# USBdimmer-breakout.net
KiCad netlist of a schematic drawn in EAGLE
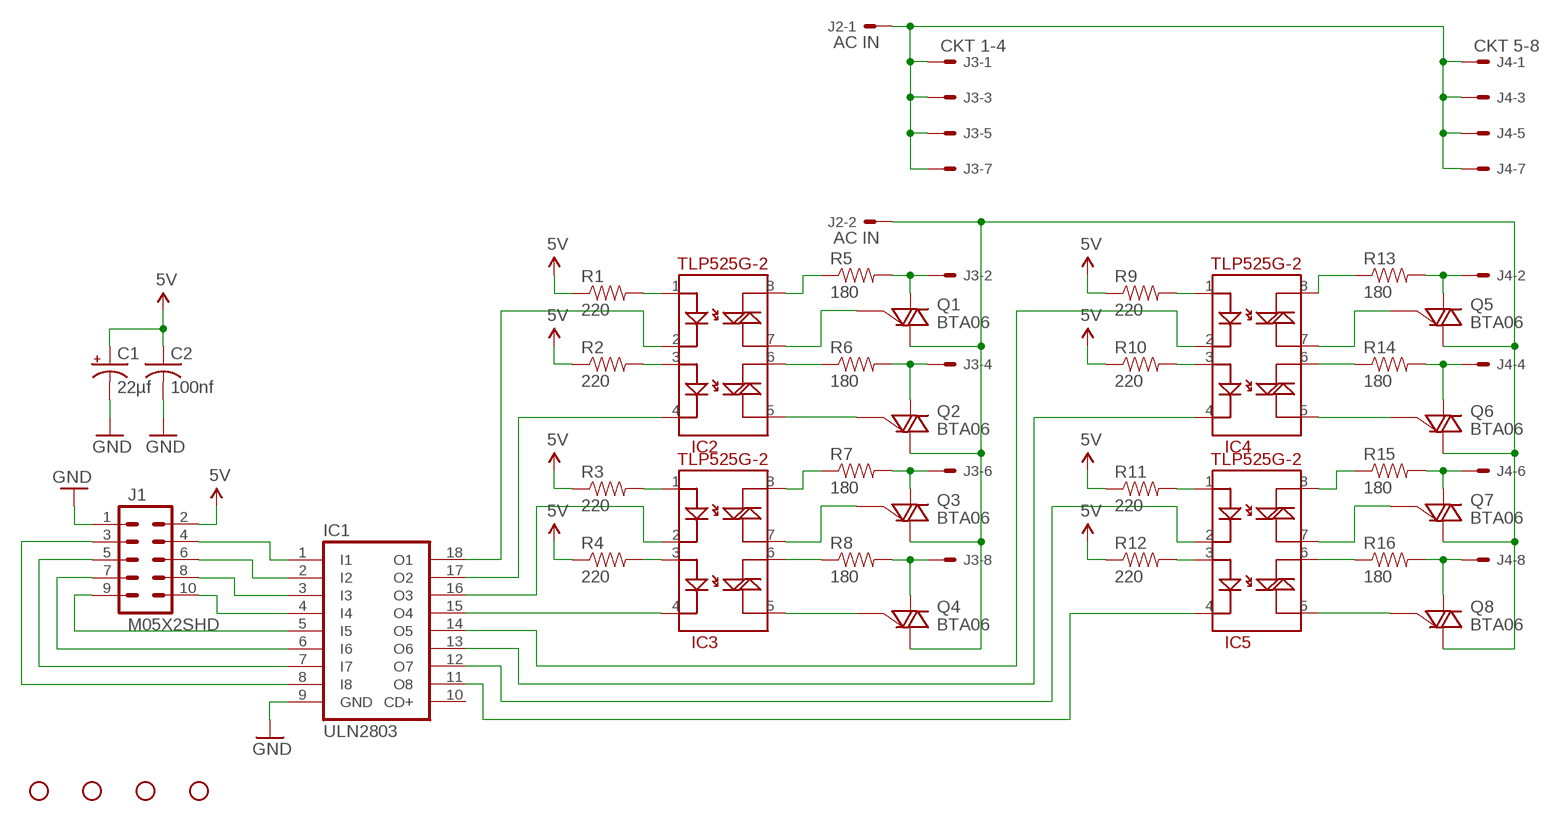
[diagram p0: schematic, sheet 1]

(export (version "E")
  (design (tool "Eeschema 10.0.6"))
  (components
    (comp (ref "C1")
      (value "22µf")
      (footprint "eagle-import:E5-8,5")
      (libsource (lib "eagle-import") (part "CPOL-USE5-8.5"))
    )
    (comp (ref "C2")
      (value "100nf")
      (footprint "eagle-import:C025-030X050")
      (libsource (lib "eagle-import") (part "C-US025-030X050"))
    )
    (comp (ref "IC1")
      (value "ULN2803")
      (footprint "eagle-import:DIL18")
      (libsource (lib "eagle-import") (part "ULN2803A"))
    )
    (comp (ref "IC2")
      (value "TLP525G-2")
      (footprint "eagle-import:DIL08")
      (libsource (lib "eagle-import") (part "TLP525G-2"))
    )
    (comp (ref "IC3")
      (value "TLP525G-2")
      (footprint "eagle-import:DIL08")
      (libsource (lib "eagle-import") (part "TLP525G-2"))
    )
    (comp (ref "IC4")
      (value "TLP525G-2")
      (footprint "eagle-import:DIL08")
      (libsource (lib "eagle-import") (part "TLP525G-2"))
    )
    (comp (ref "IC5")
      (value "TLP525G-2")
      (footprint "eagle-import:DIL08")
      (libsource (lib "eagle-import") (part "TLP525G-2"))
    )
    (comp (ref "J1")
      (value "M05X2SHD")
      (footprint "eagle-import:2X5-SHROUDED")
      (libsource (lib "eagle-import") (part "M05X2SHD"))
    )
    (comp (ref "J2")
      (value "AC IN")
      (footprint "eagle-import:KK-156-2")
      (libsource (lib "eagle-import") (part "KK-156-2"))
    )
    (comp (ref "J3")
      (value "CKT 1-4")
      (footprint "eagle-import:KK-156-8")
      (libsource (lib "eagle-import") (part "KK-156-8"))
    )
    (comp (ref "J4")
      (value "CKT 5-8")
      (footprint "eagle-import:KK-156-8")
      (libsource (lib "eagle-import") (part "KK-156-8"))
    )
    (comp (ref "Q1")
      (value "BTA06")
      (footprint "eagle-import:TO220BV")
      (libsource (lib "eagle-import") (part "BTA06"))
    )
    (comp (ref "Q2")
      (value "BTA06")
      (footprint "eagle-import:TO220BV")
      (libsource (lib "eagle-import") (part "BTA06"))
    )
    (comp (ref "Q3")
      (value "BTA06")
      (footprint "eagle-import:TO220BV")
      (libsource (lib "eagle-import") (part "BTA06"))
    )
    (comp (ref "Q4")
      (value "BTA06")
      (footprint "eagle-import:TO220BV")
      (libsource (lib "eagle-import") (part "BTA06"))
    )
    (comp (ref "Q5")
      (value "BTA06")
      (footprint "eagle-import:TO220BV")
      (libsource (lib "eagle-import") (part "BTA06"))
    )
    (comp (ref "Q6")
      (value "BTA06")
      (footprint "eagle-import:TO220BV")
      (libsource (lib "eagle-import") (part "BTA06"))
    )
    (comp (ref "Q7")
      (value "BTA06")
      (footprint "eagle-import:TO220BV")
      (libsource (lib "eagle-import") (part "BTA06"))
    )
    (comp (ref "Q8")
      (value "BTA06")
      (footprint "eagle-import:TO220BV")
      (libsource (lib "eagle-import") (part "BTA06"))
    )
    (comp (ref "R1")
      (value "220")
      (footprint "eagle-import:AXIAL-0.4")
      (libsource (lib "eagle-import") (part "RESISTORPTH-1/4W"))
    )
    (comp (ref "R2")
      (value "220")
      (footprint "eagle-import:AXIAL-0.4")
      (libsource (lib "eagle-import") (part "RESISTORPTH-1/4W"))
    )
    (comp (ref "R3")
      (value "220")
      (footprint "eagle-import:AXIAL-0.4")
      (libsource (lib "eagle-import") (part "RESISTORPTH-1/4W"))
    )
    (comp (ref "R4")
      (value "220")
      (footprint "eagle-import:AXIAL-0.4")
      (libsource (lib "eagle-import") (part "RESISTORPTH-1/4W"))
    )
    (comp (ref "R5")
      (value "180")
      (footprint "eagle-import:AXIAL-0.4")
      (libsource (lib "eagle-import") (part "RESISTORPTH-1/4W"))
    )
    (comp (ref "R6")
      (value "180")
      (footprint "eagle-import:AXIAL-0.4")
      (libsource (lib "eagle-import") (part "RESISTORPTH-1/4W"))
    )
    (comp (ref "R7")
      (value "180")
      (footprint "eagle-import:AXIAL-0.4")
      (libsource (lib "eagle-import") (part "RESISTORPTH-1/4W"))
    )
    (comp (ref "R8")
      (value "180")
      (footprint "eagle-import:AXIAL-0.4")
      (libsource (lib "eagle-import") (part "RESISTORPTH-1/4W"))
    )
    (comp (ref "R9")
      (value "220")
      (footprint "eagle-import:AXIAL-0.4")
      (libsource (lib "eagle-import") (part "RESISTORPTH-1/4W"))
    )
    (comp (ref "R10")
      (value "220")
      (footprint "eagle-import:AXIAL-0.4")
      (libsource (lib "eagle-import") (part "RESISTORPTH-1/4W"))
    )
    (comp (ref "R11")
      (value "220")
      (footprint "eagle-import:AXIAL-0.4")
      (libsource (lib "eagle-import") (part "RESISTORPTH-1/4W"))
    )
    (comp (ref "R12")
      (value "220")
      (footprint "eagle-import:AXIAL-0.4")
      (libsource (lib "eagle-import") (part "RESISTORPTH-1/4W"))
    )
    (comp (ref "R13")
      (value "180")
      (footprint "eagle-import:AXIAL-0.4")
      (libsource (lib "eagle-import") (part "RESISTORPTH-1/4W"))
    )
    (comp (ref "R14")
      (value "180")
      (footprint "eagle-import:AXIAL-0.4")
      (libsource (lib "eagle-import") (part "RESISTORPTH-1/4W"))
    )
    (comp (ref "R15")
      (value "180")
      (footprint "eagle-import:AXIAL-0.4")
      (libsource (lib "eagle-import") (part "RESISTORPTH-1/4W"))
    )
    (comp (ref "R16")
      (value "180")
      (footprint "eagle-import:AXIAL-0.4")
      (libsource (lib "eagle-import") (part "RESISTORPTH-1/4W"))
    )
    (comp (ref "STANDOFF1")
      (value "STAND-OFF")
      (footprint "eagle-import:STAND-OFF")
      (libsource (lib "eagle-import") (part "STAND-OFF"))
    )
    (comp (ref "STANDOFF2")
      (value "STAND-OFF")
      (footprint "eagle-import:STAND-OFF")
      (libsource (lib "eagle-import") (part "STAND-OFF"))
    )
    (comp (ref "STANDOFF3")
      (value "STAND-OFF")
      (footprint "eagle-import:STAND-OFF")
      (libsource (lib "eagle-import") (part "STAND-OFF"))
    )
    (comp (ref "STANDOFF4")
      (value "STAND-OFF")
      (footprint "eagle-import:STAND-OFF")
      (libsource (lib "eagle-import") (part "STAND-OFF"))
    )
  )
  (nets
    (net (code "1") (name "5V") (class "Default")
      (node (ref "C1") (pin "+") (pinfunction "+_+") (pintype "passive"))
      (node (ref "C2") (pin "1") (pinfunction "1_1") (pintype "passive"))
      (node (ref "J1") (pin "2") (pinfunction "2_2") (pintype "passive"))
      (node (ref "R1") (pin "P$1") (pinfunction "1_P$1") (pintype "passive"))
      (node (ref "R10") (pin "P$1") (pinfunction "1_P$1") (pintype "passive"))
      (node (ref "R11") (pin "P$1") (pinfunction "1_P$1") (pintype "passive"))
      (node (ref "R12") (pin "P$1") (pinfunction "1_P$1") (pintype "passive"))
      (node (ref "R2") (pin "P$1") (pinfunction "1_P$1") (pintype "passive"))
      (node (ref "R3") (pin "P$1") (pinfunction "1_P$1") (pintype "passive"))
      (node (ref "R4") (pin "P$1") (pinfunction "1_P$1") (pintype "passive"))
      (node (ref "R9") (pin "P$1") (pinfunction "1_P$1") (pintype "passive"))
    )
    (net (code "2") (name "GND") (class "Default")
      (node (ref "C1") (pin "-") (pinfunction "-_-") (pintype "passive"))
      (node (ref "C2") (pin "2") (pinfunction "2_2") (pintype "passive"))
      (node (ref "IC1") (pin "9") (pinfunction "GND_9") (pintype "power_in"))
      (node (ref "J1") (pin "1") (pinfunction "1_1") (pintype "passive"))
    )
    (net (code "3") (name "Net-(IC1-I1)") (class "Default")
      (node (ref "IC1") (pin "1") (pinfunction "I1_1") (pintype "input"))
      (node (ref "J1") (pin "4") (pinfunction "4_4") (pintype "passive"))
    )
    (net (code "4") (name "Net-(IC1-I2)") (class "Default")
      (node (ref "IC1") (pin "2") (pinfunction "I2_2") (pintype "input"))
      (node (ref "J1") (pin "6") (pinfunction "6_6") (pintype "passive"))
    )
    (net (code "5") (name "Net-(IC1-I3)") (class "Default")
      (node (ref "IC1") (pin "3") (pinfunction "I3_3") (pintype "input"))
      (node (ref "J1") (pin "8") (pinfunction "8_8") (pintype "passive"))
    )
    (net (code "6") (name "Net-(IC1-I4)") (class "Default")
      (node (ref "IC1") (pin "4") (pinfunction "I4_4") (pintype "input"))
      (node (ref "J1") (pin "10") (pinfunction "10_10") (pintype "passive"))
    )
    (net (code "7") (name "Net-(IC1-I5)") (class "Default")
      (node (ref "IC1") (pin "5") (pinfunction "I5_5") (pintype "input"))
      (node (ref "J1") (pin "9") (pinfunction "9_9") (pintype "passive"))
    )
    (net (code "8") (name "Net-(IC1-I6)") (class "Default")
      (node (ref "IC1") (pin "6") (pinfunction "I6_6") (pintype "input"))
      (node (ref "J1") (pin "7") (pinfunction "7_7") (pintype "passive"))
    )
    (net (code "9") (name "Net-(IC1-I7)") (class "Default")
      (node (ref "IC1") (pin "7") (pinfunction "I7_7") (pintype "input"))
      (node (ref "J1") (pin "5") (pinfunction "5_5") (pintype "passive"))
    )
    (net (code "10") (name "Net-(IC1-I8)") (class "Default")
      (node (ref "IC1") (pin "8") (pinfunction "I8_8") (pintype "input"))
      (node (ref "J1") (pin "3") (pinfunction "3_3") (pintype "passive"))
    )
    (net (code "11") (name "Net-(IC1-O1)") (class "Default")
      (node (ref "IC1") (pin "18") (pinfunction "O1_18") (pintype "open_collector"))
      (node (ref "IC2") (pin "2") (pinfunction "K1_2") (pintype "bidirectional"))
    )
    (net (code "12") (name "Net-(IC1-O2)") (class "Default")
      (node (ref "IC1") (pin "17") (pinfunction "O2_17") (pintype "open_collector"))
      (node (ref "IC2") (pin "4") (pinfunction "K2_4") (pintype "bidirectional"))
    )
    (net (code "13") (name "Net-(IC1-O3)") (class "Default")
      (node (ref "IC1") (pin "16") (pinfunction "O3_16") (pintype "open_collector"))
      (node (ref "IC3") (pin "2") (pinfunction "K1_2") (pintype "bidirectional"))
    )
    (net (code "14") (name "Net-(IC1-O4)") (class "Default")
      (node (ref "IC1") (pin "15") (pinfunction "O4_15") (pintype "open_collector"))
      (node (ref "IC3") (pin "4") (pinfunction "K2_4") (pintype "bidirectional"))
    )
    (net (code "15") (name "Net-(IC1-O5)") (class "Default")
      (node (ref "IC1") (pin "14") (pinfunction "O5_14") (pintype "open_collector"))
      (node (ref "IC4") (pin "2") (pinfunction "K1_2") (pintype "bidirectional"))
    )
    (net (code "16") (name "Net-(IC1-O6)") (class "Default")
      (node (ref "IC1") (pin "13") (pinfunction "O6_13") (pintype "open_collector"))
      (node (ref "IC4") (pin "4") (pinfunction "K2_4") (pintype "bidirectional"))
    )
    (net (code "17") (name "Net-(IC1-O7)") (class "Default")
      (node (ref "IC1") (pin "12") (pinfunction "O7_12") (pintype "open_collector"))
      (node (ref "IC5") (pin "2") (pinfunction "K1_2") (pintype "bidirectional"))
    )
    (net (code "18") (name "Net-(IC1-O8)") (class "Default")
      (node (ref "IC1") (pin "11") (pinfunction "O8_11") (pintype "open_collector"))
      (node (ref "IC5") (pin "4") (pinfunction "K2_4") (pintype "bidirectional"))
    )
    (net (code "19") (name "Net-(IC2-A1)") (class "Default")
      (node (ref "IC2") (pin "1") (pinfunction "A1_1") (pintype "bidirectional"))
      (node (ref "R1") (pin "P$2") (pinfunction "2_P$2") (pintype "passive"))
    )
    (net (code "20") (name "Net-(IC2-A2)") (class "Default")
      (node (ref "IC2") (pin "3") (pinfunction "A2_3") (pintype "bidirectional"))
      (node (ref "R2") (pin "P$2") (pinfunction "2_P$2") (pintype "passive"))
    )
    (net (code "21") (name "Net-(IC2-MT11)") (class "Default")
      (node (ref "IC2") (pin "8") (pinfunction "MT11_8") (pintype "bidirectional"))
      (node (ref "R5") (pin "P$1") (pinfunction "1_P$1") (pintype "passive"))
    )
    (net (code "22") (name "Net-(IC2-MT12)") (class "Default")
      (node (ref "IC2") (pin "7") (pinfunction "MT12_7") (pintype "bidirectional"))
      (node (ref "Q1") (pin "3") (pinfunction "G_3") (pintype "input"))
    )
    (net (code "23") (name "Net-(IC2-MT21)") (class "Default")
      (node (ref "IC2") (pin "6") (pinfunction "MT21_6") (pintype "bidirectional"))
      (node (ref "R6") (pin "P$1") (pinfunction "1_P$1") (pintype "passive"))
    )
    (net (code "24") (name "Net-(IC2-MT22)") (class "Default")
      (node (ref "IC2") (pin "5") (pinfunction "MT22_5") (pintype "bidirectional"))
      (node (ref "Q2") (pin "3") (pinfunction "G_3") (pintype "input"))
    )
    (net (code "25") (name "Net-(IC3-A1)") (class "Default")
      (node (ref "IC3") (pin "1") (pinfunction "A1_1") (pintype "bidirectional"))
      (node (ref "R3") (pin "P$2") (pinfunction "2_P$2") (pintype "passive"))
    )
    (net (code "26") (name "Net-(IC3-A2)") (class "Default")
      (node (ref "IC3") (pin "3") (pinfunction "A2_3") (pintype "bidirectional"))
      (node (ref "R4") (pin "P$2") (pinfunction "2_P$2") (pintype "passive"))
    )
    (net (code "27") (name "Net-(IC3-MT11)") (class "Default")
      (node (ref "IC3") (pin "8") (pinfunction "MT11_8") (pintype "bidirectional"))
      (node (ref "R7") (pin "P$1") (pinfunction "1_P$1") (pintype "passive"))
    )
    (net (code "28") (name "Net-(IC3-MT12)") (class "Default")
      (node (ref "IC3") (pin "7") (pinfunction "MT12_7") (pintype "bidirectional"))
      (node (ref "Q3") (pin "3") (pinfunction "G_3") (pintype "input"))
    )
    (net (code "29") (name "Net-(IC3-MT21)") (class "Default")
      (node (ref "IC3") (pin "6") (pinfunction "MT21_6") (pintype "bidirectional"))
      (node (ref "R8") (pin "P$1") (pinfunction "1_P$1") (pintype "passive"))
    )
    (net (code "30") (name "Net-(IC3-MT22)") (class "Default")
      (node (ref "IC3") (pin "5") (pinfunction "MT22_5") (pintype "bidirectional"))
      (node (ref "Q4") (pin "3") (pinfunction "G_3") (pintype "input"))
    )
    (net (code "31") (name "Net-(IC4-A1)") (class "Default")
      (node (ref "IC4") (pin "1") (pinfunction "A1_1") (pintype "bidirectional"))
      (node (ref "R9") (pin "P$2") (pinfunction "2_P$2") (pintype "passive"))
    )
    (net (code "32") (name "Net-(IC4-A2)") (class "Default")
      (node (ref "IC4") (pin "3") (pinfunction "A2_3") (pintype "bidirectional"))
      (node (ref "R10") (pin "P$2") (pinfunction "2_P$2") (pintype "passive"))
    )
    (net (code "33") (name "Net-(IC4-MT11)") (class "Default")
      (node (ref "IC4") (pin "8") (pinfunction "MT11_8") (pintype "bidirectional"))
      (node (ref "R13") (pin "P$1") (pinfunction "1_P$1") (pintype "passive"))
    )
    (net (code "34") (name "Net-(IC4-MT12)") (class "Default")
      (node (ref "IC4") (pin "7") (pinfunction "MT12_7") (pintype "bidirectional"))
      (node (ref "Q5") (pin "3") (pinfunction "G_3") (pintype "input"))
    )
    (net (code "35") (name "Net-(IC4-MT21)") (class "Default")
      (node (ref "IC4") (pin "6") (pinfunction "MT21_6") (pintype "bidirectional"))
      (node (ref "R14") (pin "P$1") (pinfunction "1_P$1") (pintype "passive"))
    )
    (net (code "36") (name "Net-(IC4-MT22)") (class "Default")
      (node (ref "IC4") (pin "5") (pinfunction "MT22_5") (pintype "bidirectional"))
      (node (ref "Q6") (pin "3") (pinfunction "G_3") (pintype "input"))
    )
    (net (code "37") (name "Net-(IC5-A1)") (class "Default")
      (node (ref "IC5") (pin "1") (pinfunction "A1_1") (pintype "bidirectional"))
      (node (ref "R11") (pin "P$2") (pinfunction "2_P$2") (pintype "passive"))
    )
    (net (code "38") (name "Net-(IC5-A2)") (class "Default")
      (node (ref "IC5") (pin "3") (pinfunction "A2_3") (pintype "bidirectional"))
      (node (ref "R12") (pin "P$2") (pinfunction "2_P$2") (pintype "passive"))
    )
    (net (code "39") (name "Net-(IC5-MT11)") (class "Default")
      (node (ref "IC5") (pin "8") (pinfunction "MT11_8") (pintype "bidirectional"))
      (node (ref "R15") (pin "P$1") (pinfunction "1_P$1") (pintype "passive"))
    )
    (net (code "40") (name "Net-(IC5-MT12)") (class "Default")
      (node (ref "IC5") (pin "7") (pinfunction "MT12_7") (pintype "bidirectional"))
      (node (ref "Q7") (pin "3") (pinfunction "G_3") (pintype "input"))
    )
    (net (code "41") (name "Net-(IC5-MT21)") (class "Default")
      (node (ref "IC5") (pin "6") (pinfunction "MT21_6") (pintype "bidirectional"))
      (node (ref "R16") (pin "P$1") (pinfunction "1_P$1") (pintype "passive"))
    )
    (net (code "42") (name "Net-(IC5-MT22)") (class "Default")
      (node (ref "IC5") (pin "5") (pinfunction "MT22_5") (pintype "bidirectional"))
      (node (ref "Q8") (pin "3") (pinfunction "G_3") (pintype "input"))
    )
    (net (code "43") (name "Net-(J2A-S)") (class "Default")
      (node (ref "J2") (pin "1") (pinfunction "S_1") (pintype "passive"))
      (node (ref "J3") (pin "1") (pinfunction "S_1") (pintype "passive"))
      (node (ref "J3") (pin "3") (pinfunction "S_3") (pintype "passive"))
      (node (ref "J3") (pin "5") (pinfunction "S_5") (pintype "passive"))
      (node (ref "J3") (pin "7") (pinfunction "S_7") (pintype "passive"))
      (node (ref "J4") (pin "1") (pinfunction "S_1") (pintype "passive"))
      (node (ref "J4") (pin "3") (pinfunction "S_3") (pintype "passive"))
      (node (ref "J4") (pin "5") (pinfunction "S_5") (pintype "passive"))
      (node (ref "J4") (pin "7") (pinfunction "S_7") (pintype "passive"))
    )
    (net (code "44") (name "Net-(J2B-S)") (class "Default")
      (node (ref "J2") (pin "2") (pinfunction "S_2") (pintype "passive"))
      (node (ref "Q1") (pin "2") (pinfunction "MT2_2") (pintype "bidirectional"))
      (node (ref "Q2") (pin "2") (pinfunction "MT2_2") (pintype "bidirectional"))
      (node (ref "Q3") (pin "2") (pinfunction "MT2_2") (pintype "bidirectional"))
      (node (ref "Q4") (pin "2") (pinfunction "MT2_2") (pintype "bidirectional"))
      (node (ref "Q5") (pin "2") (pinfunction "MT2_2") (pintype "bidirectional"))
      (node (ref "Q6") (pin "2") (pinfunction "MT2_2") (pintype "bidirectional"))
      (node (ref "Q7") (pin "2") (pinfunction "MT2_2") (pintype "bidirectional"))
      (node (ref "Q8") (pin "2") (pinfunction "MT2_2") (pintype "bidirectional"))
    )
    (net (code "45") (name "Net-(J3B-S)") (class "Default")
      (node (ref "J3") (pin "2") (pinfunction "S_2") (pintype "passive"))
      (node (ref "Q1") (pin "1") (pinfunction "MT1_1") (pintype "bidirectional"))
      (node (ref "R5") (pin "P$2") (pinfunction "2_P$2") (pintype "passive"))
    )
    (net (code "46") (name "Net-(J3D-S)") (class "Default")
      (node (ref "J3") (pin "4") (pinfunction "S_4") (pintype "passive"))
      (node (ref "Q2") (pin "1") (pinfunction "MT1_1") (pintype "bidirectional"))
      (node (ref "R6") (pin "P$2") (pinfunction "2_P$2") (pintype "passive"))
    )
    (net (code "47") (name "Net-(J3F-S)") (class "Default")
      (node (ref "J3") (pin "6") (pinfunction "S_6") (pintype "passive"))
      (node (ref "Q3") (pin "1") (pinfunction "MT1_1") (pintype "bidirectional"))
      (node (ref "R7") (pin "P$2") (pinfunction "2_P$2") (pintype "passive"))
    )
    (net (code "48") (name "Net-(J3H-S)") (class "Default")
      (node (ref "J3") (pin "8") (pinfunction "S_8") (pintype "passive"))
      (node (ref "Q4") (pin "1") (pinfunction "MT1_1") (pintype "bidirectional"))
      (node (ref "R8") (pin "P$2") (pinfunction "2_P$2") (pintype "passive"))
    )
    (net (code "49") (name "Net-(J4B-S)") (class "Default")
      (node (ref "J4") (pin "2") (pinfunction "S_2") (pintype "passive"))
      (node (ref "Q5") (pin "1") (pinfunction "MT1_1") (pintype "bidirectional"))
      (node (ref "R13") (pin "P$2") (pinfunction "2_P$2") (pintype "passive"))
    )
    (net (code "50") (name "Net-(J4D-S)") (class "Default")
      (node (ref "J4") (pin "4") (pinfunction "S_4") (pintype "passive"))
      (node (ref "Q6") (pin "1") (pinfunction "MT1_1") (pintype "bidirectional"))
      (node (ref "R14") (pin "P$2") (pinfunction "2_P$2") (pintype "passive"))
    )
    (net (code "51") (name "Net-(J4F-S)") (class "Default")
      (node (ref "J4") (pin "6") (pinfunction "S_6") (pintype "passive"))
      (node (ref "Q7") (pin "1") (pinfunction "MT1_1") (pintype "bidirectional"))
      (node (ref "R15") (pin "P$2") (pinfunction "2_P$2") (pintype "passive"))
    )
    (net (code "52") (name "Net-(J4H-S)") (class "Default")
      (node (ref "J4") (pin "8") (pinfunction "S_8") (pintype "passive"))
      (node (ref "Q8") (pin "1") (pinfunction "MT1_1") (pintype "bidirectional"))
      (node (ref "R16") (pin "P$2") (pinfunction "2_P$2") (pintype "passive"))
    )
    (net (code "53") (name "unconnected-(IC1-CD+-Pad10)") (class "Default")
      (node (ref "IC1") (pin "10") (pinfunction "CD+_10") (pintype "passive"))
    )
  )
)
